# AMC.net
KiCad netlist of a schematic drawn in Altium Designer
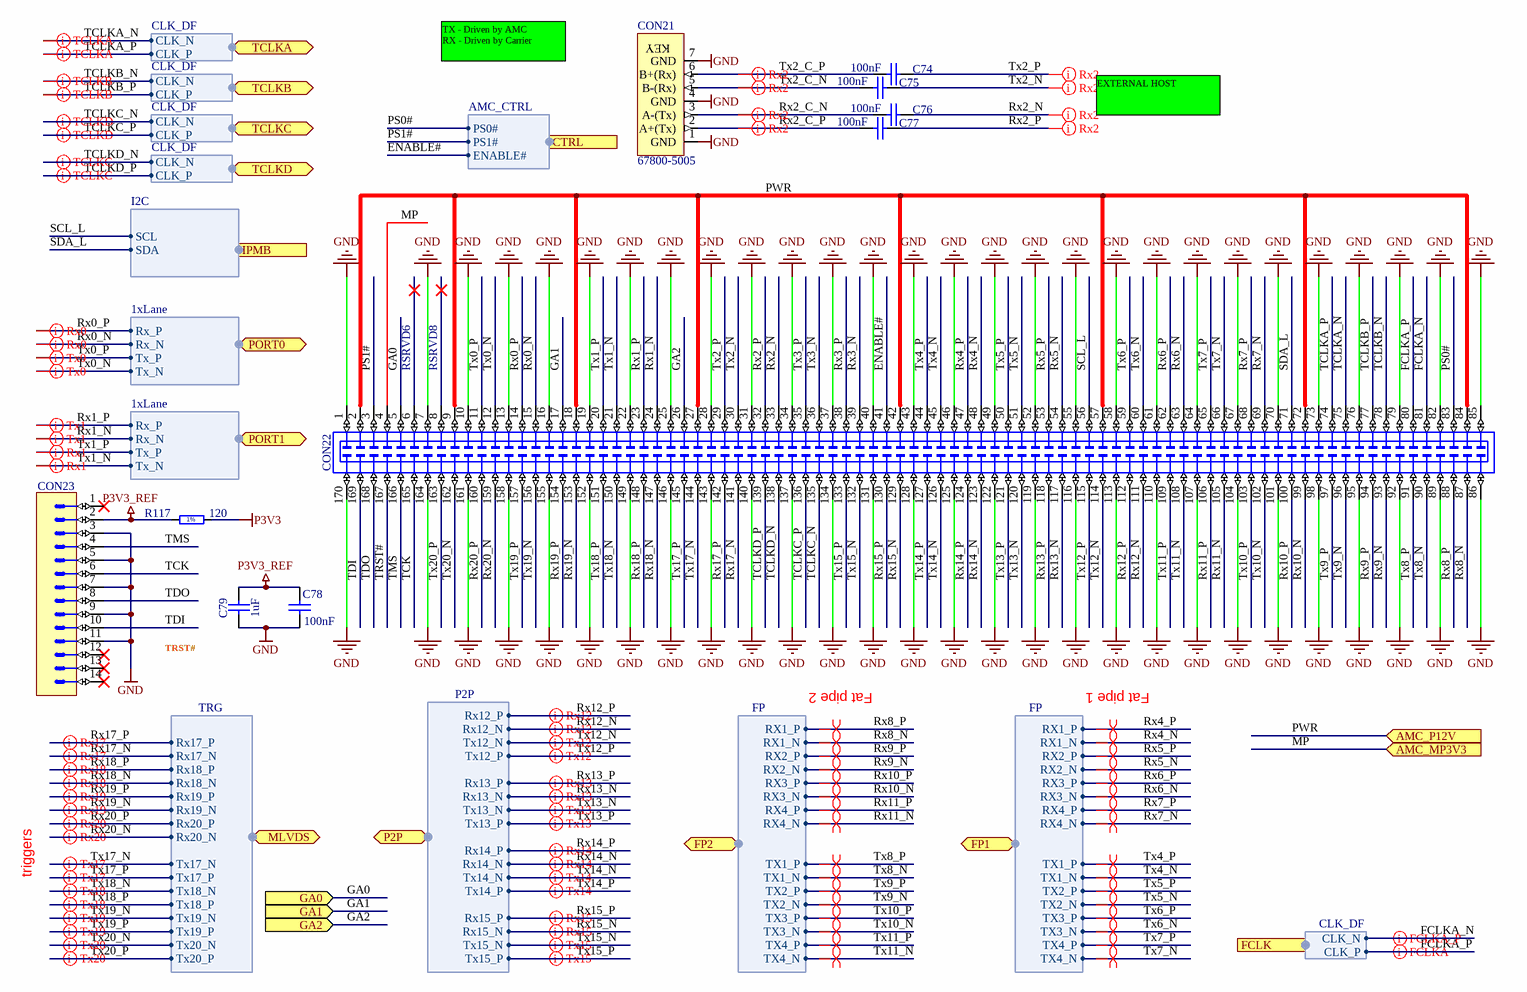
[diagram p0: AMC.SchDoc]

(export (version "E")
  (design (tool "Eeschema 10.0.6"))
  (components
    (comp (ref "C74")
      (value "100nF")
      (footprint "CAPC0603X33N")
      (description "Non-polarised capacitor")
      (fields
        (field (name "PART NUMBER") "CC0201_100NF_6.3V_10%_X5R")
        (field (name "VOLTAGE") "6.3V")
        (field (name "AUTHOR") "CERN DEM JLC")
      )
      (libsource (lib "Capacitors") (part "Capacitor - non polarized"))
    )
    (comp (ref "C75")
      (value "100nF")
      (footprint "CAPC0603X33N")
      (description "Non-polarised capacitor")
      (fields
        (field (name "PART NUMBER") "CC0201_100NF_6.3V_10%_X5R")
        (field (name "VOLTAGE") "6.3V")
        (field (name "AUTHOR") "CERN DEM JLC")
      )
      (libsource (lib "Capacitors") (part "Capacitor - non polarized"))
    )
    (comp (ref "C76")
      (value "100nF")
      (footprint "CAPC0603X33N")
      (description "Non-polarised capacitor")
      (fields
        (field (name "PART NUMBER") "CC0201_100NF_6.3V_10%_X5R")
        (field (name "VOLTAGE") "6.3V")
        (field (name "AUTHOR") "CERN DEM JLC")
      )
      (libsource (lib "Capacitors") (part "Capacitor - non polarized"))
    )
    (comp (ref "C77")
      (value "100nF")
      (footprint "CAPC0603X33N")
      (description "Non-polarised capacitor")
      (fields
        (field (name "PART NUMBER") "CC0201_100NF_6.3V_10%_X5R")
        (field (name "VOLTAGE") "6.3V")
        (field (name "AUTHOR") "CERN DEM JLC")
      )
      (libsource (lib "Capacitors") (part "Capacitor - non polarized"))
    )
    (comp (ref "C78")
      (value "100nF")
      (footprint "CAPC0603X33N")
      (description "Non-polarised capacitor")
      (fields
        (field (name "PART NUMBER") "CC0201_100NF_6.3V_10%_X5R")
        (field (name "VOLTAGE") "6.3V")
        (field (name "AUTHOR") "CERN DEM JLC")
      )
      (libsource (lib "Capacitors") (part "Capacitor - non polarized"))
    )
    (comp (ref "C79")
      (value "1uF")
      (footprint "CAPC1608X87N")
      (description "Non-polarised capacitor")
      (fields
        (field (name "PART NUMBER") "CC0603_1UF_25V_10%_X7R")
        (field (name "VOLTAGE") "25V")
        (field (name "AUTHOR") "CERN DEM JLC")
      )
      (libsource (lib "Capacitors") (part "Capacitor - non polarized"))
    )
    (comp (ref "CON21")
      (value "67800-5005")
      (footprint "CON_SATA_V")
      (description "SATA conenctor  PCB Molex")
      (libsource (lib "AMC_FMC_Carrier") (part "CON_SATA_V"))
    )
    (comp (ref "CON22")
      (value "SAMTEC_MTCA-085-02-S-DV-SMT-K-TR")
      (footprint "SAMTEC_MTCA-085-02-S-DV-SMT-K-TR")
      (description "170 Poles,  Micro TCA (Telecom Computing Architecture) Edge Card Socket")
      (fields
        (field (name "MANUFACTURER") "SAMTEC")
        (field (name "MANUFACTURER PART NUMBER") "MTCA-085-02-S-DV-SMT-K-TR")
        (field (name "AUTHOR") "CERN DEM JLC")
      )
      (libsource (lib "Connectors") (part "Micro TCA Female 170"))
    )
    (comp (ref "CON23")
      (value "MOLEX_87832-1420")
      (footprint "MOLEX_87832-1420")
      (description "Connector 14 Male")
      (fields
        (field (name "MANUFACTURER") "MOLEX")
        (field (name "MANUFACTURER PART NUMBER") "87832-1420")
        (field (name "AUTHOR") "CERN DEM JLC")
      )
      (libsource (lib "Connectors") (part "Connector 14 Male"))
    )
    (comp (ref "R117")
      (value "120")
      (footprint "RESC1005X40N")
      (description "Resistor - 1%")
      (fields
        (field (name "PART NUMBER") "R0402_120R_1%_0.0625W_100PPM")
        (field (name "POWER") "0.0625W")
        (field (name "AUTHOR") "CERN DEM JLC")
      )
      (libsource (lib "Resistors") (part "Resistor - 1%"))
    )
  )
  (nets
    (net (code "8") (name "/ENABLE#") (class "Default")
      (node (ref "CON22") (pin "41") (pinfunction "41_41") (pintype "bidirectional"))
    )
    (net (code "9") (name "/FCLKA_N") (class "Default")
      (node (ref "CON22") (pin "81") (pinfunction "81_81") (pintype "bidirectional"))
    )
    (net (code "10") (name "/FCLKA_P") (class "Default")
      (node (ref "CON22") (pin "80") (pinfunction "80_80") (pintype "bidirectional"))
    )
    (net (code "11") (name "/GA0") (class "Default")
      (node (ref "CON22") (pin "5") (pinfunction "5_5") (pintype "bidirectional"))
    )
    (net (code "12") (name "/GA1") (class "Default")
      (node (ref "CON22") (pin "17") (pinfunction "17_17") (pintype "bidirectional"))
    )
    (net (code "13") (name "/GA2") (class "Default")
      (node (ref "CON22") (pin "26") (pinfunction "26_26") (pintype "bidirectional"))
    )
    (net (code "14") (name "/MP") (class "Default")
      (node (ref "CON22") (pin "4") (pinfunction "4_4") (pintype "bidirectional"))
    )
    (net (code "15") (name "/PS0#") (class "Default")
      (node (ref "CON22") (pin "83") (pinfunction "83_83") (pintype "bidirectional"))
    )
    (net (code "16") (name "/PS1#") (class "Default")
      (node (ref "CON22") (pin "3") (pinfunction "3_3") (pintype "bidirectional"))
    )
    (net (code "17") (name "/PWR") (class "Default")
      (node (ref "CON22") (pin "18") (pinfunction "18_18") (pintype "bidirectional"))
      (node (ref "CON22") (pin "2") (pinfunction "2_2") (pintype "bidirectional"))
      (node (ref "CON22") (pin "27") (pinfunction "27_27") (pintype "bidirectional"))
      (node (ref "CON22") (pin "42") (pinfunction "42_42") (pintype "bidirectional"))
      (node (ref "CON22") (pin "57") (pinfunction "57_57") (pintype "bidirectional"))
      (node (ref "CON22") (pin "72") (pinfunction "72_72") (pintype "bidirectional"))
      (node (ref "CON22") (pin "84") (pinfunction "84_84") (pintype "bidirectional"))
      (node (ref "CON22") (pin "9") (pinfunction "9_9") (pintype "bidirectional"))
    )
    (net (code "18") (name "/Rx0_N") (class "Default")
      (node (ref "CON22") (pin "15") (pinfunction "15_15") (pintype "bidirectional"))
    )
    (net (code "19") (name "/Rx0_P") (class "Default")
      (node (ref "CON22") (pin "14") (pinfunction "14_14") (pintype "bidirectional"))
    )
    (net (code "20") (name "/Rx1_N") (class "Default")
      (node (ref "CON22") (pin "24") (pinfunction "24_24") (pintype "bidirectional"))
    )
    (net (code "21") (name "/Rx1_P") (class "Default")
      (node (ref "CON22") (pin "23") (pinfunction "23_23") (pintype "bidirectional"))
    )
    (net (code "22") (name "/Rx2_C_N") (class "Default")
      (node (ref "C76") (pin "1") (pinfunction "1_1") (pintype "passive"))
      (node (ref "CON21") (pin "3") (pinfunction "A-(Tx)_3") (pintype "output"))
    )
    (net (code "23") (name "/Rx2_C_P") (class "Default")
      (node (ref "C77") (pin "1") (pinfunction "1_1") (pintype "passive"))
      (node (ref "CON21") (pin "2") (pinfunction "A+(Tx)_2") (pintype "output"))
    )
    (net (code "24") (name "/Rx2_N") (class "Default")
      (node (ref "C76") (pin "2") (pinfunction "2_2") (pintype "passive"))
      (node (ref "CON22") (pin "33") (pinfunction "33_33") (pintype "bidirectional"))
    )
    (net (code "25") (name "/Rx2_P") (class "Default")
      (node (ref "C77") (pin "2") (pinfunction "2_2") (pintype "passive"))
      (node (ref "CON22") (pin "32") (pinfunction "32_32") (pintype "bidirectional"))
    )
    (net (code "26") (name "/Rx3_N") (class "Default")
      (node (ref "CON22") (pin "39") (pinfunction "39_39") (pintype "bidirectional"))
    )
    (net (code "27") (name "/Rx3_P") (class "Default")
      (node (ref "CON22") (pin "38") (pinfunction "38_38") (pintype "bidirectional"))
    )
    (net (code "28") (name "/Rx4_N") (class "Default")
      (node (ref "CON22") (pin "48") (pinfunction "48_48") (pintype "bidirectional"))
    )
    (net (code "29") (name "/Rx4_P") (class "Default")
      (node (ref "CON22") (pin "47") (pinfunction "47_47") (pintype "bidirectional"))
    )
    (net (code "30") (name "/Rx5_N") (class "Default")
      (node (ref "CON22") (pin "54") (pinfunction "54_54") (pintype "bidirectional"))
    )
    (net (code "31") (name "/Rx5_P") (class "Default")
      (node (ref "CON22") (pin "53") (pinfunction "53_53") (pintype "bidirectional"))
    )
    (net (code "32") (name "/Rx6_N") (class "Default")
      (node (ref "CON22") (pin "63") (pinfunction "63_63") (pintype "bidirectional"))
    )
    (net (code "33") (name "/Rx6_P") (class "Default")
      (node (ref "CON22") (pin "62") (pinfunction "62_62") (pintype "bidirectional"))
    )
    (net (code "34") (name "/Rx7_N") (class "Default")
      (node (ref "CON22") (pin "69") (pinfunction "69_69") (pintype "bidirectional"))
    )
    (net (code "35") (name "/Rx7_P") (class "Default")
      (node (ref "CON22") (pin "68") (pinfunction "68_68") (pintype "bidirectional"))
    )
    (net (code "36") (name "/Rx8_N") (class "Default")
      (node (ref "CON22") (pin "87") (pinfunction "87_87") (pintype "bidirectional"))
    )
    (net (code "37") (name "/Rx8_P") (class "Default")
      (node (ref "CON22") (pin "88") (pinfunction "88_88") (pintype "bidirectional"))
    )
    (net (code "38") (name "/Rx9_N") (class "Default")
      (node (ref "CON22") (pin "93") (pinfunction "93_93") (pintype "bidirectional"))
    )
    (net (code "39") (name "/Rx9_P") (class "Default")
      (node (ref "CON22") (pin "94") (pinfunction "94_94") (pintype "bidirectional"))
    )
    (net (code "40") (name "/Rx10_N") (class "Default")
      (node (ref "CON22") (pin "99") (pinfunction "99_99") (pintype "bidirectional"))
    )
    (net (code "41") (name "/Rx10_P") (class "Default")
      (node (ref "CON22") (pin "100") (pinfunction "100_100") (pintype "bidirectional"))
    )
    (net (code "42") (name "/Rx11_N") (class "Default")
      (node (ref "CON22") (pin "105") (pinfunction "105_105") (pintype "bidirectional"))
    )
    (net (code "43") (name "/Rx11_P") (class "Default")
      (node (ref "CON22") (pin "106") (pinfunction "106_106") (pintype "bidirectional"))
    )
    (net (code "44") (name "/Rx12_N") (class "Default")
      (node (ref "CON22") (pin "111") (pinfunction "111_111") (pintype "bidirectional"))
    )
    (net (code "45") (name "/Rx12_P") (class "Default")
      (node (ref "CON22") (pin "112") (pinfunction "112_112") (pintype "bidirectional"))
    )
    (net (code "46") (name "/Rx13_N") (class "Default")
      (node (ref "CON22") (pin "117") (pinfunction "117_117") (pintype "bidirectional"))
    )
    (net (code "47") (name "/Rx13_P") (class "Default")
      (node (ref "CON22") (pin "118") (pinfunction "118_118") (pintype "bidirectional"))
    )
    (net (code "48") (name "/Rx14_N") (class "Default")
      (node (ref "CON22") (pin "123") (pinfunction "123_123") (pintype "bidirectional"))
    )
    (net (code "49") (name "/Rx14_P") (class "Default")
      (node (ref "CON22") (pin "124") (pinfunction "124_124") (pintype "bidirectional"))
    )
    (net (code "50") (name "/Rx15_N") (class "Default")
      (node (ref "CON22") (pin "129") (pinfunction "129_129") (pintype "bidirectional"))
    )
    (net (code "51") (name "/Rx15_P") (class "Default")
      (node (ref "CON22") (pin "130") (pinfunction "130_130") (pintype "bidirectional"))
    )
    (net (code "52") (name "/Rx17_N") (class "Default")
      (node (ref "CON22") (pin "141") (pinfunction "141_141") (pintype "bidirectional"))
    )
    (net (code "53") (name "/Rx17_P") (class "Default")
      (node (ref "CON22") (pin "142") (pinfunction "142_142") (pintype "bidirectional"))
    )
    (net (code "54") (name "/Rx18_N") (class "Default")
      (node (ref "CON22") (pin "147") (pinfunction "147_147") (pintype "bidirectional"))
    )
    (net (code "55") (name "/Rx18_P") (class "Default")
      (node (ref "CON22") (pin "148") (pinfunction "148_148") (pintype "bidirectional"))
    )
    (net (code "56") (name "/Rx19_N") (class "Default")
      (node (ref "CON22") (pin "153") (pinfunction "153_153") (pintype "bidirectional"))
    )
    (net (code "57") (name "/Rx19_P") (class "Default")
      (node (ref "CON22") (pin "154") (pinfunction "154_154") (pintype "bidirectional"))
    )
    (net (code "58") (name "/Rx20_N") (class "Default")
      (node (ref "CON22") (pin "159") (pinfunction "159_159") (pintype "bidirectional"))
    )
    (net (code "59") (name "/Rx20_P") (class "Default")
      (node (ref "CON22") (pin "160") (pinfunction "160_160") (pintype "bidirectional"))
    )
    (net (code "60") (name "/SCL_L") (class "Default")
      (node (ref "CON22") (pin "56") (pinfunction "56_56") (pintype "bidirectional"))
    )
    (net (code "61") (name "/SDA_L") (class "Default")
      (node (ref "CON22") (pin "71") (pinfunction "71_71") (pintype "bidirectional"))
    )
    (net (code "62") (name "/TCK") (class "Default")
      (node (ref "CON22") (pin "165") (pinfunction "165_165") (pintype "bidirectional"))
      (node (ref "CON23") (pin "6") (pinfunction "6_6") (pintype "bidirectional"))
    )
    (net (code "63") (name "/TCLKA_N") (class "Default")
      (node (ref "CON22") (pin "75") (pinfunction "75_75") (pintype "bidirectional"))
    )
    (net (code "64") (name "/TCLKA_P") (class "Default")
      (node (ref "CON22") (pin "74") (pinfunction "74_74") (pintype "bidirectional"))
    )
    (net (code "65") (name "/TCLKB_N") (class "Default")
      (node (ref "CON22") (pin "78") (pinfunction "78_78") (pintype "bidirectional"))
    )
    (net (code "66") (name "/TCLKB_P") (class "Default")
      (node (ref "CON22") (pin "77") (pinfunction "77_77") (pintype "bidirectional"))
    )
    (net (code "67") (name "/TCLKC_N") (class "Default")
      (node (ref "CON22") (pin "135") (pinfunction "135_135") (pintype "bidirectional"))
    )
    (net (code "68") (name "/TCLKC_P") (class "Default")
      (node (ref "CON22") (pin "136") (pinfunction "136_136") (pintype "bidirectional"))
    )
    (net (code "69") (name "/TCLKD_N") (class "Default")
      (node (ref "CON22") (pin "138") (pinfunction "138_138") (pintype "bidirectional"))
    )
    (net (code "70") (name "/TCLKD_P") (class "Default")
      (node (ref "CON22") (pin "139") (pinfunction "139_139") (pintype "bidirectional"))
    )
    (net (code "71") (name "/TDI") (class "Default")
      (node (ref "CON22") (pin "169") (pinfunction "169_169") (pintype "bidirectional"))
      (node (ref "CON23") (pin "10") (pinfunction "10_10") (pintype "bidirectional"))
    )
    (net (code "72") (name "/TDO") (class "Default")
      (node (ref "CON22") (pin "168") (pinfunction "168_168") (pintype "bidirectional"))
      (node (ref "CON23") (pin "8") (pinfunction "8_8") (pintype "bidirectional"))
    )
    (net (code "73") (name "/TMS") (class "Default")
      (node (ref "CON22") (pin "166") (pinfunction "166_166") (pintype "bidirectional"))
      (node (ref "CON23") (pin "4") (pinfunction "4_4") (pintype "bidirectional"))
    )
    (net (code "74") (name "/TRST#") (class "Default")
      (node (ref "CON22") (pin "167") (pinfunction "167_167") (pintype "bidirectional"))
    )
    (net (code "75") (name "/Tx0_N") (class "Default")
      (node (ref "CON22") (pin "12") (pinfunction "12_12") (pintype "bidirectional"))
    )
    (net (code "76") (name "/Tx0_P") (class "Default")
      (node (ref "CON22") (pin "11") (pinfunction "11_11") (pintype "bidirectional"))
    )
    (net (code "77") (name "/Tx1_N") (class "Default")
      (node (ref "CON22") (pin "21") (pinfunction "21_21") (pintype "bidirectional"))
    )
    (net (code "78") (name "/Tx1_P") (class "Default")
      (node (ref "CON22") (pin "20") (pinfunction "20_20") (pintype "bidirectional"))
    )
    (net (code "79") (name "/Tx2_C_N") (class "Default")
      (node (ref "C75") (pin "1") (pinfunction "1_1") (pintype "passive"))
      (node (ref "CON21") (pin "5") (pinfunction "B-(Rx)_5") (pintype "input"))
    )
    (net (code "80") (name "/Tx2_C_P") (class "Default")
      (node (ref "C74") (pin "1") (pinfunction "1_1") (pintype "passive"))
      (node (ref "CON21") (pin "6") (pinfunction "B+(Rx)_6") (pintype "input"))
    )
    (net (code "81") (name "/Tx2_N") (class "Default")
      (node (ref "C75") (pin "2") (pinfunction "2_2") (pintype "passive"))
      (node (ref "CON22") (pin "30") (pinfunction "30_30") (pintype "bidirectional"))
    )
    (net (code "82") (name "/Tx2_P") (class "Default")
      (node (ref "C74") (pin "2") (pinfunction "2_2") (pintype "passive"))
      (node (ref "CON22") (pin "29") (pinfunction "29_29") (pintype "bidirectional"))
    )
    (net (code "83") (name "/Tx3_N") (class "Default")
      (node (ref "CON22") (pin "36") (pinfunction "36_36") (pintype "bidirectional"))
    )
    (net (code "84") (name "/Tx3_P") (class "Default")
      (node (ref "CON22") (pin "35") (pinfunction "35_35") (pintype "bidirectional"))
    )
    (net (code "85") (name "/Tx4_N") (class "Default")
      (node (ref "CON22") (pin "45") (pinfunction "45_45") (pintype "bidirectional"))
    )
    (net (code "86") (name "/Tx4_P") (class "Default")
      (node (ref "CON22") (pin "44") (pinfunction "44_44") (pintype "bidirectional"))
    )
    (net (code "87") (name "/Tx5_N") (class "Default")
      (node (ref "CON22") (pin "51") (pinfunction "51_51") (pintype "bidirectional"))
    )
    (net (code "88") (name "/Tx5_P") (class "Default")
      (node (ref "CON22") (pin "50") (pinfunction "50_50") (pintype "bidirectional"))
    )
    (net (code "89") (name "/Tx6_N") (class "Default")
      (node (ref "CON22") (pin "60") (pinfunction "60_60") (pintype "bidirectional"))
    )
    (net (code "90") (name "/Tx6_P") (class "Default")
      (node (ref "CON22") (pin "59") (pinfunction "59_59") (pintype "bidirectional"))
    )
    (net (code "91") (name "/Tx7_N") (class "Default")
      (node (ref "CON22") (pin "66") (pinfunction "66_66") (pintype "bidirectional"))
    )
    (net (code "92") (name "/Tx7_P") (class "Default")
      (node (ref "CON22") (pin "65") (pinfunction "65_65") (pintype "bidirectional"))
    )
    (net (code "93") (name "/Tx8_N") (class "Default")
      (node (ref "CON22") (pin "90") (pinfunction "90_90") (pintype "bidirectional"))
    )
    (net (code "94") (name "/Tx8_P") (class "Default")
      (node (ref "CON22") (pin "91") (pinfunction "91_91") (pintype "bidirectional"))
    )
    (net (code "95") (name "/Tx9_N") (class "Default")
      (node (ref "CON22") (pin "96") (pinfunction "96_96") (pintype "bidirectional"))
    )
    (net (code "96") (name "/Tx9_P") (class "Default")
      (node (ref "CON22") (pin "97") (pinfunction "97_97") (pintype "bidirectional"))
    )
    (net (code "97") (name "/Tx10_N") (class "Default")
      (node (ref "CON22") (pin "102") (pinfunction "102_102") (pintype "bidirectional"))
    )
    (net (code "98") (name "/Tx10_P") (class "Default")
      (node (ref "CON22") (pin "103") (pinfunction "103_103") (pintype "bidirectional"))
    )
    (net (code "99") (name "/Tx11_N") (class "Default")
      (node (ref "CON22") (pin "108") (pinfunction "108_108") (pintype "bidirectional"))
    )
    (net (code "100") (name "/Tx11_P") (class "Default")
      (node (ref "CON22") (pin "109") (pinfunction "109_109") (pintype "bidirectional"))
    )
    (net (code "101") (name "/Tx12_N") (class "Default")
      (node (ref "CON22") (pin "114") (pinfunction "114_114") (pintype "bidirectional"))
    )
    (net (code "102") (name "/Tx12_P") (class "Default")
      (node (ref "CON22") (pin "115") (pinfunction "115_115") (pintype "bidirectional"))
    )
    (net (code "103") (name "/Tx13_N") (class "Default")
      (node (ref "CON22") (pin "120") (pinfunction "120_120") (pintype "bidirectional"))
    )
    (net (code "104") (name "/Tx13_P") (class "Default")
      (node (ref "CON22") (pin "121") (pinfunction "121_121") (pintype "bidirectional"))
    )
    (net (code "105") (name "/Tx14_N") (class "Default")
      (node (ref "CON22") (pin "126") (pinfunction "126_126") (pintype "bidirectional"))
    )
    (net (code "106") (name "/Tx14_P") (class "Default")
      (node (ref "CON22") (pin "127") (pinfunction "127_127") (pintype "bidirectional"))
    )
    (net (code "107") (name "/Tx15_N") (class "Default")
      (node (ref "CON22") (pin "132") (pinfunction "132_132") (pintype "bidirectional"))
    )
    (net (code "108") (name "/Tx15_P") (class "Default")
      (node (ref "CON22") (pin "133") (pinfunction "133_133") (pintype "bidirectional"))
    )
    (net (code "109") (name "/Tx17_N") (class "Default")
      (node (ref "CON22") (pin "144") (pinfunction "144_144") (pintype "bidirectional"))
    )
    (net (code "110") (name "/Tx17_P") (class "Default")
      (node (ref "CON22") (pin "145") (pinfunction "145_145") (pintype "bidirectional"))
    )
    (net (code "111") (name "/Tx18_N") (class "Default")
      (node (ref "CON22") (pin "150") (pinfunction "150_150") (pintype "bidirectional"))
    )
    (net (code "112") (name "/Tx18_P") (class "Default")
      (node (ref "CON22") (pin "151") (pinfunction "151_151") (pintype "bidirectional"))
    )
    (net (code "113") (name "/Tx19_N") (class "Default")
      (node (ref "CON22") (pin "156") (pinfunction "156_156") (pintype "bidirectional"))
    )
    (net (code "114") (name "/Tx19_P") (class "Default")
      (node (ref "CON22") (pin "157") (pinfunction "157_157") (pintype "bidirectional"))
    )
    (net (code "115") (name "/Tx20_N") (class "Default")
      (node (ref "CON22") (pin "162") (pinfunction "162_162") (pintype "bidirectional"))
    )
    (net (code "116") (name "/Tx20_P") (class "Default")
      (node (ref "CON22") (pin "163") (pinfunction "163_163") (pintype "bidirectional"))
    )
    (net (code "124") (name "GND") (class "Default")
      (node (ref "C78") (pin "1") (pinfunction "1_1") (pintype "passive"))
      (node (ref "C79") (pin "1") (pinfunction "1_1") (pintype "passive"))
      (node (ref "CON21") (pin "1") (pinfunction "GND_1") (pintype "power_in"))
      (node (ref "CON21") (pin "4") (pinfunction "GND_4") (pintype "power_in"))
      (node (ref "CON21") (pin "7") (pinfunction "GND_7") (pintype "power_in"))
      (node (ref "CON22") (pin "1") (pinfunction "1_1") (pintype "bidirectional"))
      (node (ref "CON22") (pin "10") (pinfunction "10_10") (pintype "bidirectional"))
      (node (ref "CON22") (pin "101") (pinfunction "101_101") (pintype "bidirectional"))
      (node (ref "CON22") (pin "104") (pinfunction "104_104") (pintype "bidirectional"))
      (node (ref "CON22") (pin "107") (pinfunction "107_107") (pintype "bidirectional"))
      (node (ref "CON22") (pin "110") (pinfunction "110_110") (pintype "bidirectional"))
      (node (ref "CON22") (pin "113") (pinfunction "113_113") (pintype "bidirectional"))
      (node (ref "CON22") (pin "116") (pinfunction "116_116") (pintype "bidirectional"))
      (node (ref "CON22") (pin "119") (pinfunction "119_119") (pintype "bidirectional"))
      (node (ref "CON22") (pin "122") (pinfunction "122_122") (pintype "bidirectional"))
      (node (ref "CON22") (pin "125") (pinfunction "125_125") (pintype "bidirectional"))
      (node (ref "CON22") (pin "128") (pinfunction "128_128") (pintype "bidirectional"))
      (node (ref "CON22") (pin "13") (pinfunction "13_13") (pintype "bidirectional"))
      (node (ref "CON22") (pin "131") (pinfunction "131_131") (pintype "bidirectional"))
      (node (ref "CON22") (pin "134") (pinfunction "134_134") (pintype "bidirectional"))
      (node (ref "CON22") (pin "137") (pinfunction "137_137") (pintype "bidirectional"))
      (node (ref "CON22") (pin "140") (pinfunction "140_140") (pintype "bidirectional"))
      (node (ref "CON22") (pin "143") (pinfunction "143_143") (pintype "bidirectional"))
      (node (ref "CON22") (pin "146") (pinfunction "146_146") (pintype "bidirectional"))
      (node (ref "CON22") (pin "149") (pinfunction "149_149") (pintype "bidirectional"))
      (node (ref "CON22") (pin "152") (pinfunction "152_152") (pintype "bidirectional"))
      (node (ref "CON22") (pin "155") (pinfunction "155_155") (pintype "bidirectional"))
      (node (ref "CON22") (pin "158") (pinfunction "158_158") (pintype "bidirectional"))
      (node (ref "CON22") (pin "16") (pinfunction "16_16") (pintype "bidirectional"))
      (node (ref "CON22") (pin "161") (pinfunction "161_161") (pintype "bidirectional"))
      (node (ref "CON22") (pin "164") (pinfunction "164_164") (pintype "bidirectional"))
      (node (ref "CON22") (pin "170") (pinfunction "170_170") (pintype "bidirectional"))
      (node (ref "CON22") (pin "19") (pinfunction "19_19") (pintype "bidirectional"))
      (node (ref "CON22") (pin "22") (pinfunction "22_22") (pintype "bidirectional"))
      (node (ref "CON22") (pin "25") (pinfunction "25_25") (pintype "bidirectional"))
      (node (ref "CON22") (pin "28") (pinfunction "28_28") (pintype "bidirectional"))
      (node (ref "CON22") (pin "31") (pinfunction "31_31") (pintype "bidirectional"))
      (node (ref "CON22") (pin "34") (pinfunction "34_34") (pintype "bidirectional"))
      (node (ref "CON22") (pin "37") (pinfunction "37_37") (pintype "bidirectional"))
      (node (ref "CON22") (pin "40") (pinfunction "40_40") (pintype "bidirectional"))
      (node (ref "CON22") (pin "43") (pinfunction "43_43") (pintype "bidirectional"))
      (node (ref "CON22") (pin "46") (pinfunction "46_46") (pintype "bidirectional"))
      (node (ref "CON22") (pin "49") (pinfunction "49_49") (pintype "bidirectional"))
      (node (ref "CON22") (pin "52") (pinfunction "52_52") (pintype "bidirectional"))
      (node (ref "CON22") (pin "55") (pinfunction "55_55") (pintype "bidirectional"))
      (node (ref "CON22") (pin "58") (pinfunction "58_58") (pintype "bidirectional"))
      (node (ref "CON22") (pin "61") (pinfunction "61_61") (pintype "bidirectional"))
      (node (ref "CON22") (pin "64") (pinfunction "64_64") (pintype "bidirectional"))
      (node (ref "CON22") (pin "67") (pinfunction "67_67") (pintype "bidirectional"))
      (node (ref "CON22") (pin "7") (pinfunction "7_7") (pintype "bidirectional"))
      (node (ref "CON22") (pin "70") (pinfunction "70_70") (pintype "bidirectional"))
      (node (ref "CON22") (pin "73") (pinfunction "73_73") (pintype "bidirectional"))
      (node (ref "CON22") (pin "76") (pinfunction "76_76") (pintype "bidirectional"))
      (node (ref "CON22") (pin "79") (pinfunction "79_79") (pintype "bidirectional"))
      (node (ref "CON22") (pin "82") (pinfunction "82_82") (pintype "bidirectional"))
      (node (ref "CON22") (pin "85") (pinfunction "85_85") (pintype "bidirectional"))
      (node (ref "CON22") (pin "86") (pinfunction "86_86") (pintype "bidirectional"))
      (node (ref "CON22") (pin "89") (pinfunction "89_89") (pintype "bidirectional"))
      (node (ref "CON22") (pin "92") (pinfunction "92_92") (pintype "bidirectional"))
      (node (ref "CON22") (pin "95") (pinfunction "95_95") (pintype "bidirectional"))
      (node (ref "CON22") (pin "98") (pinfunction "98_98") (pintype "bidirectional"))
      (node (ref "CON23") (pin "11") (pinfunction "11_11") (pintype "bidirectional"))
      (node (ref "CON23") (pin "3") (pinfunction "3_3") (pintype "bidirectional"))
      (node (ref "CON23") (pin "5") (pinfunction "5_5") (pintype "bidirectional"))
      (node (ref "CON23") (pin "7") (pinfunction "7_7") (pintype "bidirectional"))
      (node (ref "CON23") (pin "9") (pinfunction "9_9") (pintype "bidirectional"))
    )
    (net (code "125") (name "P3V3") (class "Default")
      (node (ref "R117") (pin "2") (pinfunction "2_2") (pintype "passive"))
    )
    (net (code "126") (name "P3V3_REF") (class "Default")
      (node (ref "C78") (pin "2") (pinfunction "2_2") (pintype "passive"))
      (node (ref "C79") (pin "2") (pinfunction "2_2") (pintype "passive"))
      (node (ref "CON23") (pin "2") (pinfunction "2_2") (pintype "bidirectional"))
      (node (ref "R117") (pin "1") (pinfunction "1_1") (pintype "passive"))
    )
    (net (code "127") (name "unconnected-(CON22-Pad6)") (class "Default")
      (node (ref "CON22") (pin "6") (pinfunction "6_6") (pintype "bidirectional"))
    )
    (net (code "128") (name "unconnected-(CON22-Pad8)") (class "Default")
      (node (ref "CON22") (pin "8") (pinfunction "8_8") (pintype "bidirectional"))
    )
    (net (code "129") (name "unconnected-(CON23-Pad1)") (class "Default")
      (node (ref "CON23") (pin "1") (pinfunction "1_1") (pintype "bidirectional+no_connect"))
    )
    (net (code "130") (name "unconnected-(CON23-Pad12)") (class "Default")
      (node (ref "CON23") (pin "12") (pinfunction "12_12") (pintype "bidirectional+no_connect"))
    )
    (net (code "131") (name "unconnected-(CON23-Pad13)") (class "Default")
      (node (ref "CON23") (pin "13") (pinfunction "13_13") (pintype "bidirectional+no_connect"))
    )
    (net (code "132") (name "unconnected-(CON23-Pad14)") (class "Default")
      (node (ref "CON23") (pin "14") (pinfunction "14_14") (pintype "bidirectional+no_connect"))
    )
  )
)
